# octanis_eps_compact_no_OPA2333.net
KiCad netlist of a schematic drawn in EAGLE
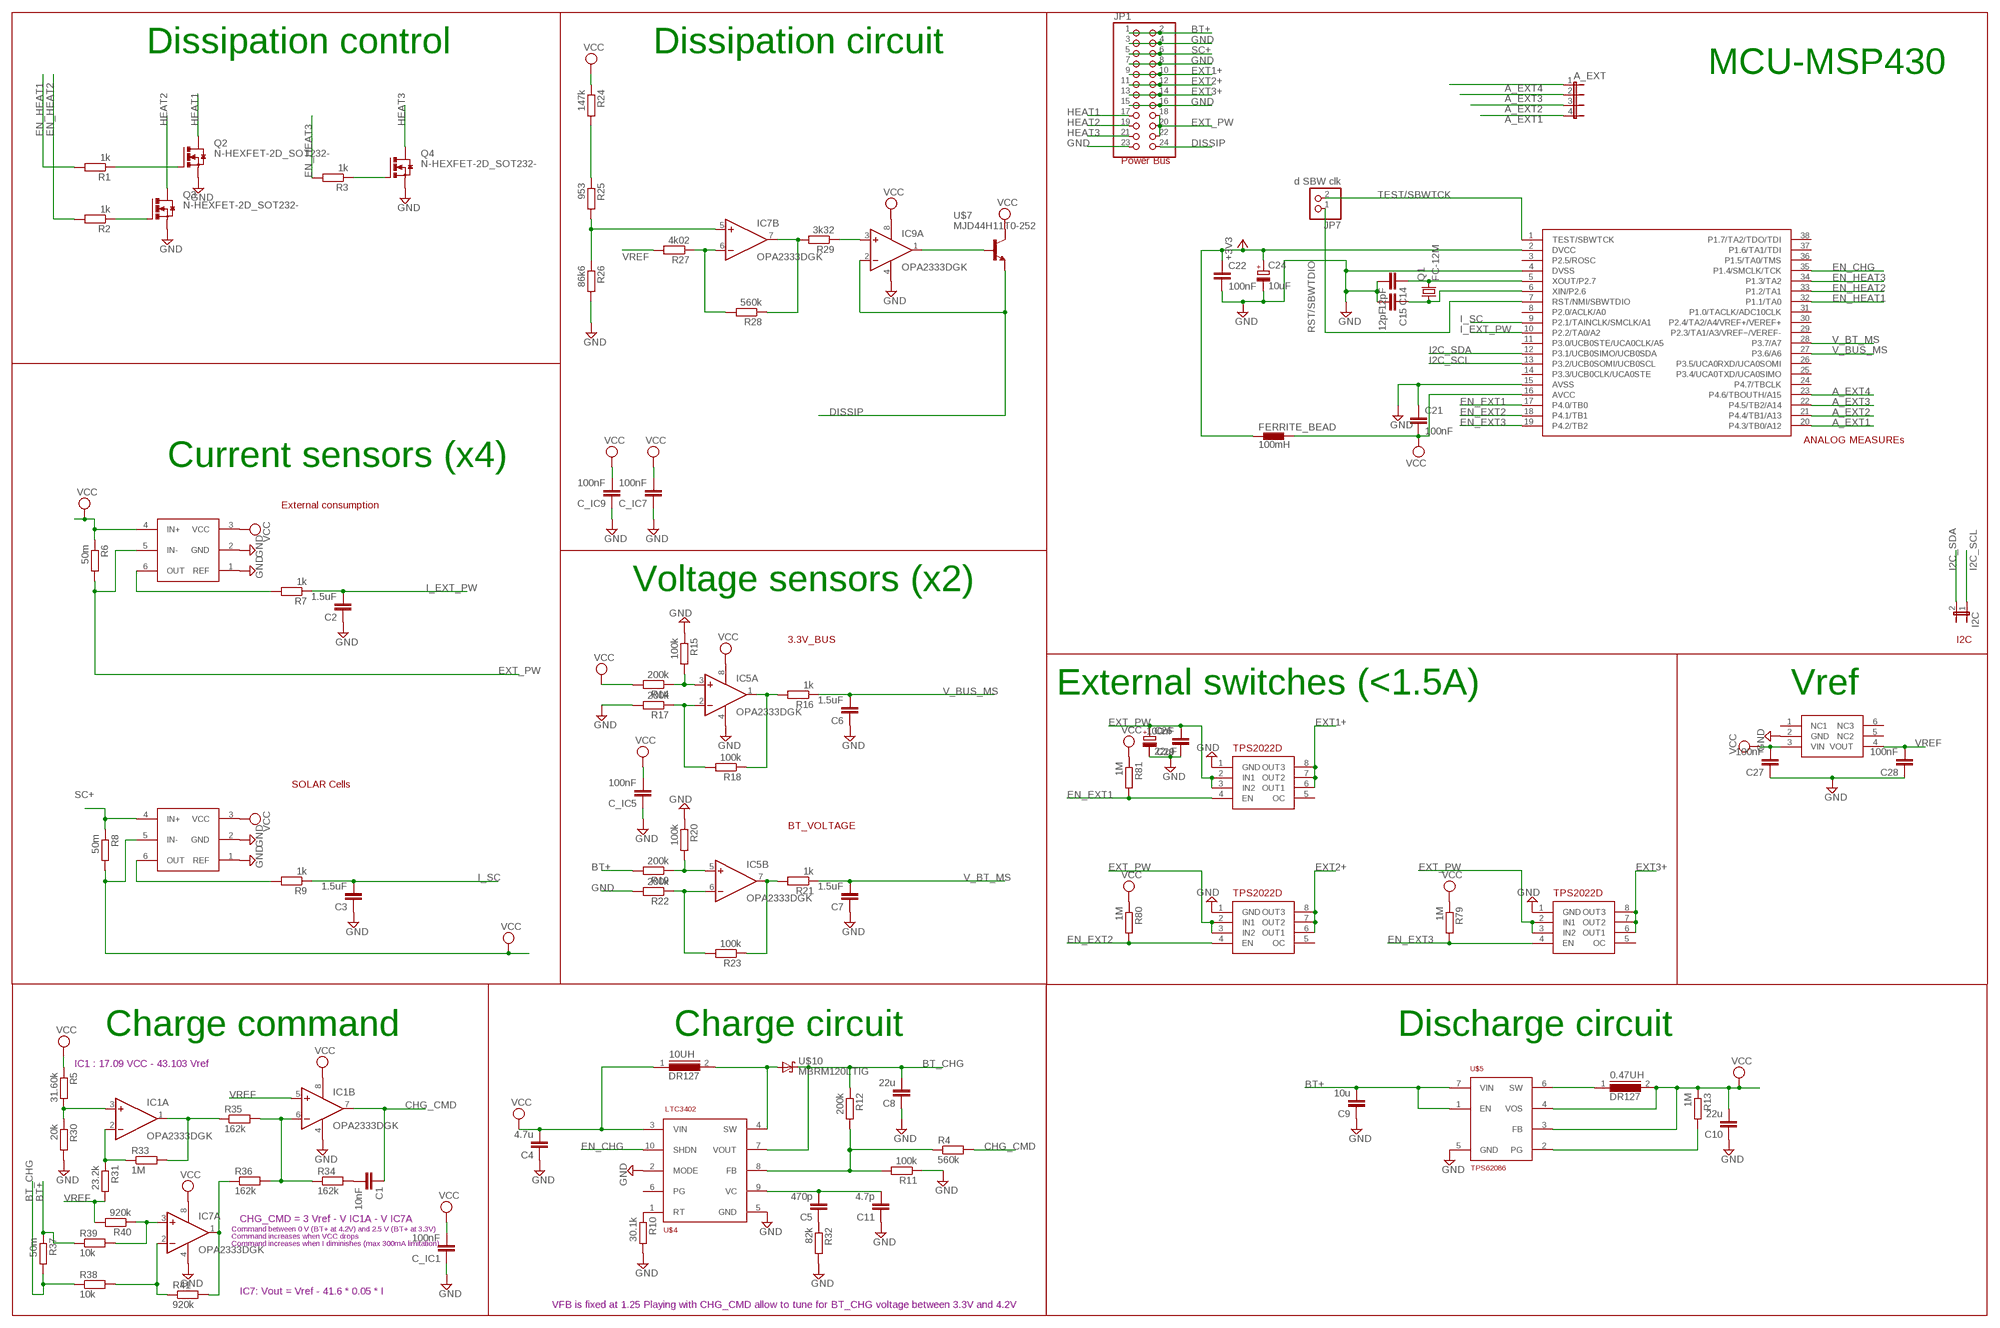
[diagram p0: schematic, sheet 1]

(export (version "E")
  (design (tool "Eeschema 10.0.6"))
  (components
    (comp (ref "0.47UH")
      (value "DR127")
      (footprint "eagle-import:DR127")
      (libsource (lib "eagle-import") (part "DR127"))
    )
    (comp (ref "10UH")
      (value "DR127")
      (footprint "eagle-import:DR127")
      (libsource (lib "eagle-import") (part "DR127"))
    )
    (comp (ref "A_EXT")
      (value "JP4E")
      (footprint "eagle-import:JP4")
      (libsource (lib "eagle-import") (part "JP4E"))
    )
    (comp (ref "C1")
      (value "10nF")
      (footprint "eagle-import:C0603")
      (libsource (lib "eagle-import") (part "C-EUC0603"))
    )
    (comp (ref "C2")
      (value "1.5uF")
      (footprint "eagle-import:C0603")
      (libsource (lib "eagle-import") (part "C-EUC0603"))
    )
    (comp (ref "C3")
      (value "1.5uF")
      (footprint "eagle-import:C0603")
      (libsource (lib "eagle-import") (part "C-EUC0603"))
    )
    (comp (ref "C4")
      (value "4.7u")
      (footprint "eagle-import:C1206")
      (libsource (lib "eagle-import") (part "C-EUC1206"))
    )
    (comp (ref "C5")
      (value "470p")
      (footprint "eagle-import:C0603")
      (libsource (lib "eagle-import") (part "C-EUC0603"))
    )
    (comp (ref "C6")
      (value "1.5uF")
      (footprint "eagle-import:C0603")
      (libsource (lib "eagle-import") (part "C-EUC0603"))
    )
    (comp (ref "C7")
      (value "1.5uF")
      (footprint "eagle-import:C0603")
      (libsource (lib "eagle-import") (part "C-EUC0603"))
    )
    (comp (ref "C8")
      (value "22u")
      (footprint "eagle-import:C0603")
      (libsource (lib "eagle-import") (part "C-EUC0603"))
    )
    (comp (ref "C9")
      (value "10u")
      (footprint "eagle-import:C1206")
      (libsource (lib "eagle-import") (part "C-EUC1206"))
    )
    (comp (ref "C10")
      (value "22u")
      (footprint "eagle-import:C1206")
      (libsource (lib "eagle-import") (part "C-EUC1206"))
    )
    (comp (ref "C11")
      (value "4.7p")
      (footprint "eagle-import:C0603")
      (libsource (lib "eagle-import") (part "C-EUC0603"))
    )
    (comp (ref "C14")
      (value "12pF")
      (footprint "eagle-import:C0603")
      (libsource (lib "eagle-import") (part "C-EUC0603"))
    )
    (comp (ref "C15")
      (value "12pF")
      (footprint "eagle-import:C0603")
      (libsource (lib "eagle-import") (part "C-EUC0603"))
    )
    (comp (ref "C21")
      (value "100nF")
      (footprint "eagle-import:C0603")
      (libsource (lib "eagle-import") (part "C-EUC0603"))
    )
    (comp (ref "C22")
      (value "100nF")
      (footprint "eagle-import:C0603")
      (libsource (lib "eagle-import") (part "C-EUC0603"))
    )
    (comp (ref "C24")
      (value "10uF")
      (footprint "eagle-import:A_3216-18R")
      (libsource (lib "eagle-import") (part "CPOL-EUA/3216-18R"))
    )
    (comp (ref "C26")
      (value "22uF")
      (footprint "eagle-import:A_3216-18R")
      (libsource (lib "eagle-import") (part "CPOL-EUA/3216-18R"))
    )
    (comp (ref "C27")
      (value "100nF")
      (footprint "eagle-import:C0603")
      (libsource (lib "eagle-import") (part "C-EUC0603"))
    )
    (comp (ref "C28")
      (value "100nF")
      (footprint "eagle-import:C0603")
      (libsource (lib "eagle-import") (part "C-EUC0603"))
    )
    (comp (ref "C29")
      (value "100nF")
      (footprint "eagle-import:C0603")
      (libsource (lib "eagle-import") (part "C-EUC0603"))
    )
    (comp (ref "C_IC1")
      (value "100nF")
      (footprint "eagle-import:C0603")
      (libsource (lib "eagle-import") (part "C-EUC0603"))
    )
    (comp (ref "C_IC5")
      (value "100nF")
      (footprint "eagle-import:C0603")
      (libsource (lib "eagle-import") (part "C-EUC0603"))
    )
    (comp (ref "C_IC7")
      (value "100nF")
      (footprint "eagle-import:C0603")
      (libsource (lib "eagle-import") (part "C-EUC0603"))
    )
    (comp (ref "C_IC9")
      (value "100nF")
      (footprint "eagle-import:C0603")
      (libsource (lib "eagle-import") (part "C-EUC0603"))
    )
    (comp (ref "FERRITE_BEAD")
      (value "100mH")
      (footprint "eagle-import:0402")
      (libsource (lib "eagle-import") (part "BLM15HD601SN1"))
    )
    (comp (ref "I2C")
      (value "JP1E")
      (footprint "eagle-import:JP1")
      (libsource (lib "eagle-import") (part "JP1E"))
    )
    (comp (ref "IC1")
      (value "OPA2333DGK")
      (footprint "eagle-import:MSOP08")
      (libsource (lib "eagle-import") (part "OPA2333DGK"))
    )
    (comp (ref "IC5")
      (value "OPA2333DGK")
      (footprint "eagle-import:MSOP08")
      (libsource (lib "eagle-import") (part "OPA2333DGK"))
    )
    (comp (ref "IC7")
      (value "OPA2333DGK")
      (footprint "eagle-import:MSOP08")
      (libsource (lib "eagle-import") (part "OPA2333DGK"))
    )
    (comp (ref "IC9")
      (value "OPA2333DGK")
      (footprint "eagle-import:MSOP08")
      (libsource (lib "eagle-import") (part "OPA2333DGK"))
    )
    (comp (ref "JP1")
      (value "PINHD-2X12")
      (footprint "eagle-import:2X12")
      (libsource (lib "eagle-import") (part "PINHD-2X12"))
    )
    (comp (ref "JP7")
      (value "d SBW clk")
      (footprint "eagle-import:1X02")
      (libsource (lib "eagle-import") (part "PINHD-1X2"))
    )
    (comp (ref "Q1")
      (value "FC-12M")
      (footprint "eagle-import:FC-12M")
      (libsource (lib "eagle-import") (part "FC-12M"))
    )
    (comp (ref "Q2")
      (value "N-HEXFET-2D_SOT232-")
      (footprint "eagle-import:SOT223")
      (libsource (lib "eagle-import") (part "N-HEXFET-2D_?-SOT232"))
    )
    (comp (ref "Q3")
      (value "N-HEXFET-2D_SOT232-")
      (footprint "eagle-import:SOT223")
      (libsource (lib "eagle-import") (part "N-HEXFET-2D_?-SOT232"))
    )
    (comp (ref "Q4")
      (value "N-HEXFET-2D_SOT232-")
      (footprint "eagle-import:SOT223")
      (libsource (lib "eagle-import") (part "N-HEXFET-2D_?-SOT232"))
    )
    (comp (ref "R1")
      (value "1k")
      (footprint "eagle-import:R0603")
      (libsource (lib "eagle-import") (part "R-EU_R0603"))
    )
    (comp (ref "R2")
      (value "1k")
      (footprint "eagle-import:R0603")
      (libsource (lib "eagle-import") (part "R-EU_R0603"))
    )
    (comp (ref "R3")
      (value "1k")
      (footprint "eagle-import:R0603")
      (libsource (lib "eagle-import") (part "R-EU_R0603"))
    )
    (comp (ref "R4")
      (value "560k")
      (footprint "eagle-import:R0603")
      (libsource (lib "eagle-import") (part "R-EU_R0603"))
    )
    (comp (ref "R5")
      (value "31.60k")
      (footprint "eagle-import:R0603")
      (libsource (lib "eagle-import") (part "R-EU_R0603"))
    )
    (comp (ref "R6")
      (value "50m")
      (footprint "eagle-import:R1206")
      (libsource (lib "eagle-import") (part "R-EU_R1206"))
    )
    (comp (ref "R7")
      (value "1k")
      (footprint "eagle-import:R0603")
      (libsource (lib "eagle-import") (part "R-EU_R0603"))
    )
    (comp (ref "R8")
      (value "50m")
      (footprint "eagle-import:R1206")
      (libsource (lib "eagle-import") (part "R-EU_R1206"))
    )
    (comp (ref "R9")
      (value "1k")
      (footprint "eagle-import:R0603")
      (libsource (lib "eagle-import") (part "R-EU_R0603"))
    )
    (comp (ref "R10")
      (value "30.1k")
      (footprint "eagle-import:R0603")
      (libsource (lib "eagle-import") (part "R-EU_R0603"))
    )
    (comp (ref "R11")
      (value "100k")
      (footprint "eagle-import:R0603")
      (libsource (lib "eagle-import") (part "R-EU_R0603"))
    )
    (comp (ref "R12")
      (value "200k")
      (footprint "eagle-import:R0603")
      (libsource (lib "eagle-import") (part "R-EU_R0603"))
    )
    (comp (ref "R13")
      (value "1M")
      (footprint "eagle-import:R0603")
      (libsource (lib "eagle-import") (part "R-EU_R0603"))
    )
    (comp (ref "R14")
      (value "200k")
      (footprint "eagle-import:R0603")
      (libsource (lib "eagle-import") (part "R-EU_R0603"))
    )
    (comp (ref "R15")
      (value "100k")
      (footprint "eagle-import:R0603")
      (libsource (lib "eagle-import") (part "R-EU_R0603"))
    )
    (comp (ref "R16")
      (value "1k")
      (footprint "eagle-import:R0603")
      (libsource (lib "eagle-import") (part "R-EU_R0603"))
    )
    (comp (ref "R17")
      (value "200k")
      (footprint "eagle-import:R0603")
      (libsource (lib "eagle-import") (part "R-EU_R0603"))
    )
    (comp (ref "R18")
      (value "100k")
      (footprint "eagle-import:R0603")
      (libsource (lib "eagle-import") (part "R-EU_R0603"))
    )
    (comp (ref "R19")
      (value "200k")
      (footprint "eagle-import:R0603")
      (libsource (lib "eagle-import") (part "R-EU_R0603"))
    )
    (comp (ref "R20")
      (value "100k")
      (footprint "eagle-import:R0603")
      (libsource (lib "eagle-import") (part "R-EU_R0603"))
    )
    (comp (ref "R21")
      (value "1k")
      (footprint "eagle-import:R0603")
      (libsource (lib "eagle-import") (part "R-EU_R0603"))
    )
    (comp (ref "R22")
      (value "200k")
      (footprint "eagle-import:R0603")
      (libsource (lib "eagle-import") (part "R-EU_R0603"))
    )
    (comp (ref "R23")
      (value "100k")
      (footprint "eagle-import:R0603")
      (libsource (lib "eagle-import") (part "R-EU_R0603"))
    )
    (comp (ref "R24")
      (value "147k")
      (footprint "eagle-import:R0603")
      (libsource (lib "eagle-import") (part "R-EU_R0603"))
    )
    (comp (ref "R25")
      (value "953")
      (footprint "eagle-import:R0603")
      (libsource (lib "eagle-import") (part "R-EU_R0603"))
    )
    (comp (ref "R26")
      (value "86k6")
      (footprint "eagle-import:R0603")
      (libsource (lib "eagle-import") (part "R-EU_R0603"))
    )
    (comp (ref "R27")
      (value "4k02")
      (footprint "eagle-import:R0603")
      (libsource (lib "eagle-import") (part "R-EU_R0603"))
    )
    (comp (ref "R28")
      (value "560k")
      (footprint "eagle-import:R0603")
      (libsource (lib "eagle-import") (part "R-EU_R0603"))
    )
    (comp (ref "R29")
      (value "3k32")
      (footprint "eagle-import:R0603")
      (libsource (lib "eagle-import") (part "R-EU_R0603"))
    )
    (comp (ref "R30")
      (value "20k")
      (footprint "eagle-import:R0603")
      (libsource (lib "eagle-import") (part "R-EU_R0603"))
    )
    (comp (ref "R31")
      (value "23.2k")
      (footprint "eagle-import:R0603")
      (libsource (lib "eagle-import") (part "R-EU_R0603"))
    )
    (comp (ref "R32")
      (value "82k")
      (footprint "eagle-import:R0603")
      (libsource (lib "eagle-import") (part "R-EU_R0603"))
    )
    (comp (ref "R33")
      (value "1M")
      (footprint "eagle-import:R0603")
      (libsource (lib "eagle-import") (part "R-EU_R0603"))
    )
    (comp (ref "R34")
      (value "162k")
      (footprint "eagle-import:R0603")
      (libsource (lib "eagle-import") (part "R-EU_R0603"))
    )
    (comp (ref "R35")
      (value "162k")
      (footprint "eagle-import:R0603")
      (libsource (lib "eagle-import") (part "R-EU_R0603"))
    )
    (comp (ref "R36")
      (value "162k")
      (footprint "eagle-import:R0603")
      (libsource (lib "eagle-import") (part "R-EU_R0603"))
    )
    (comp (ref "R37")
      (value "50m")
      (footprint "eagle-import:R1206")
      (libsource (lib "eagle-import") (part "R-EU_R1206"))
    )
    (comp (ref "R38")
      (value "10k")
      (footprint "eagle-import:R0603")
      (libsource (lib "eagle-import") (part "R-EU_R0603"))
    )
    (comp (ref "R39")
      (value "10k")
      (footprint "eagle-import:R0603")
      (libsource (lib "eagle-import") (part "R-EU_R0603"))
    )
    (comp (ref "R40")
      (value "920k")
      (footprint "eagle-import:R0603")
      (libsource (lib "eagle-import") (part "R-EU_R0603"))
    )
    (comp (ref "R41")
      (value "920k")
      (footprint "eagle-import:R0603")
      (libsource (lib "eagle-import") (part "R-EU_R0603"))
    )
    (comp (ref "R79")
      (value "1M")
      (footprint "eagle-import:R0603")
      (libsource (lib "eagle-import") (part "R-EU_R0603"))
    )
    (comp (ref "R80")
      (value "1M")
      (footprint "eagle-import:R0603")
      (libsource (lib "eagle-import") (part "R-EU_R0603"))
    )
    (comp (ref "R81")
      (value "1M")
      (footprint "eagle-import:R0603")
      (libsource (lib "eagle-import") (part "R-EU_R0603"))
    )
    (comp (ref "U$2")
      (value "INA213")
      (footprint "eagle-import:SC70-6")
      (libsource (lib "eagle-import") (part "INA213"))
    )
    (comp (ref "U$3")
      (value "INA213")
      (footprint "eagle-import:SC70-6")
      (libsource (lib "eagle-import") (part "INA213"))
    )
    (comp (ref "U$4")
      (value "LTC3402")
      (footprint "eagle-import:MSOP10")
      (libsource (lib "eagle-import") (part "LTC3402"))
    )
    (comp (ref "U$5")
      (value "TPS62086")
      (footprint "eagle-import:QFN-7")
      (libsource (lib "eagle-import") (part "TPS62086"))
    )
    (comp (ref "U$6")
      (value "MSP430G2544")
      (footprint "eagle-import:TSSOP38")
      (libsource (lib "eagle-import") (part "MSP430G2544"))
    )
    (comp (ref "U$7")
      (value "MJD44H11T0-252")
      (footprint "eagle-import:TO252")
      (libsource (lib "eagle-import") (part "MJD44H11T0-252"))
    )
    (comp (ref "U$10")
      (value "MBRM120LTIG")
      (footprint "eagle-import:DO216AA")
      (libsource (lib "eagle-import") (part "MBRM120LTIG"))
    )
    (comp (ref "U$16")
      (value "TPS2022D")
      (footprint "eagle-import:SO8")
      (libsource (lib "eagle-import") (part "TPS2022D"))
    )
    (comp (ref "U$17")
      (value "TPS2022D")
      (footprint "eagle-import:SO8")
      (libsource (lib "eagle-import") (part "TPS2022D"))
    )
    (comp (ref "U$18")
      (value "TPS2022D")
      (footprint "eagle-import:SO8")
      (libsource (lib "eagle-import") (part "TPS2022D"))
    )
    (comp (ref "U$19")
      (value "ADR127B")
      (footprint "eagle-import:TSOT23-6")
      (libsource (lib "eagle-import") (part "ADR127B"))
    )
  )
  (nets
    (net (code "1") (name "+3V3") (class "Default")
      (node (ref "C22") (pin "1") (pinfunction "1_1") (pintype "passive"))
      (node (ref "C24") (pin "+") (pinfunction "+_+") (pintype "passive"))
      (node (ref "FERRITE_BEAD") (pin "1") (pinfunction "1_1") (pintype "passive"))
      (node (ref "U$6") (pin "2") (pinfunction "DVCC_2") (pintype "bidirectional"))
    )
    (net (code "2") (name "/A_EXT1") (class "Default")
      (node (ref "A_EXT") (pin "4") (pinfunction "4_4") (pintype "passive"))
      (node (ref "U$6") (pin "20") (pinfunction "P4.3/TB0/A12_20") (pintype "bidirectional"))
    )
    (net (code "3") (name "/A_EXT2") (class "Default")
      (node (ref "A_EXT") (pin "3") (pinfunction "3_3") (pintype "passive"))
      (node (ref "U$6") (pin "21") (pinfunction "P4.4/TB1/A13_21") (pintype "bidirectional"))
    )
    (net (code "4") (name "/A_EXT3") (class "Default")
      (node (ref "A_EXT") (pin "2") (pinfunction "2_2") (pintype "passive"))
      (node (ref "U$6") (pin "22") (pinfunction "P4.5/TB2/A14_22") (pintype "bidirectional"))
    )
    (net (code "5") (name "/A_EXT4") (class "Default")
      (node (ref "A_EXT") (pin "1") (pinfunction "1_1") (pintype "passive"))
      (node (ref "U$6") (pin "23") (pinfunction "P4.6/TBOUTH/A15_23") (pintype "bidirectional"))
    )
    (net (code "6") (name "/BT+") (class "Default")
      (node (ref "C9") (pin "2") (pinfunction "2_2") (pintype "passive"))
      (node (ref "JP1") (pin "1") (pinfunction "1_1") (pintype "passive"))
      (node (ref "JP1") (pin "2") (pinfunction "2_2") (pintype "passive"))
      (node (ref "R19") (pin "2") (pinfunction "2_2") (pintype "passive"))
      (node (ref "R37") (pin "1") (pinfunction "1_1") (pintype "passive"))
      (node (ref "R39") (pin "1") (pinfunction "1_1") (pintype "passive"))
      (node (ref "U$5") (pin "1") (pinfunction "EN_1") (pintype "bidirectional"))
      (node (ref "U$5") (pin "7") (pinfunction "VIN_7") (pintype "bidirectional"))
    )
    (net (code "7") (name "/BT_CHG") (class "Default")
      (node (ref "C8") (pin "2") (pinfunction "2_2") (pintype "passive"))
      (node (ref "R12") (pin "1") (pinfunction "1_1") (pintype "passive"))
      (node (ref "R37") (pin "2") (pinfunction "2_2") (pintype "passive"))
      (node (ref "R38") (pin "1") (pinfunction "1_1") (pintype "passive"))
      (node (ref "U$10") (pin "C") (pinfunction "K_C") (pintype "passive"))
      (node (ref "U$4") (pin "7") (pinfunction "VOUT_7") (pintype "bidirectional"))
    )
    (net (code "8") (name "/CHG_CMD") (class "Default")
      (node (ref "C1") (pin "1") (pinfunction "1_1") (pintype "passive"))
      (node (ref "IC1") (pin "7") (pinfunction "OUT_7") (pintype "output"))
      (node (ref "R4") (pin "2") (pinfunction "2_2") (pintype "passive"))
    )
    (net (code "9") (name "/DISSIP") (class "Default")
      (node (ref "IC9") (pin "2") (pinfunction "-IN_2") (pintype "input"))
      (node (ref "JP1") (pin "24") (pinfunction "24_24") (pintype "passive"))
      (node (ref "U$7") (pin "3") (pinfunction "E_3") (pintype "passive"))
    )
    (net (code "10") (name "/EN_CHG") (class "Default")
      (node (ref "U$4") (pin "10") (pinfunction "SHDN_10") (pintype "bidirectional"))
      (node (ref "U$6") (pin "35") (pinfunction "P1.4/SMCLK/TCK_35") (pintype "bidirectional"))
    )
    (net (code "11") (name "/EN_EXT1") (class "Default")
      (node (ref "R81") (pin "2") (pinfunction "2_2") (pintype "passive"))
      (node (ref "U$16") (pin "4") (pinfunction "EN_4") (pintype "bidirectional"))
      (node (ref "U$6") (pin "17") (pinfunction "P4.0/TB0_17") (pintype "bidirectional"))
    )
    (net (code "12") (name "/EN_EXT2") (class "Default")
      (node (ref "R80") (pin "2") (pinfunction "2_2") (pintype "passive"))
      (node (ref "U$17") (pin "4") (pinfunction "EN_4") (pintype "bidirectional"))
      (node (ref "U$6") (pin "18") (pinfunction "P4.1/TB1_18") (pintype "bidirectional"))
    )
    (net (code "13") (name "/EN_EXT3") (class "Default")
      (node (ref "R79") (pin "2") (pinfunction "2_2") (pintype "passive"))
      (node (ref "U$18") (pin "4") (pinfunction "EN_4") (pintype "bidirectional"))
      (node (ref "U$6") (pin "19") (pinfunction "P4.2/TB2_19") (pintype "bidirectional"))
    )
    (net (code "14") (name "/EN_HEAT1") (class "Default")
      (node (ref "R1") (pin "2") (pinfunction "2_2") (pintype "passive"))
      (node (ref "U$6") (pin "32") (pinfunction "P1.1/TA0_32") (pintype "bidirectional"))
    )
    (net (code "15") (name "/EN_HEAT2") (class "Default")
      (node (ref "R2") (pin "2") (pinfunction "2_2") (pintype "passive"))
      (node (ref "U$6") (pin "33") (pinfunction "P1.2/TA1_33") (pintype "bidirectional"))
    )
    (net (code "16") (name "/EN_HEAT3") (class "Default")
      (node (ref "R3") (pin "2") (pinfunction "2_2") (pintype "passive"))
      (node (ref "U$6") (pin "34") (pinfunction "P1.3/TA2_34") (pintype "bidirectional"))
    )
    (net (code "17") (name "/EXT1+") (class "Default")
      (node (ref "JP1") (pin "10") (pinfunction "10_10") (pintype "passive"))
      (node (ref "JP1") (pin "9") (pinfunction "9_9") (pintype "passive"))
      (node (ref "U$16") (pin "6") (pinfunction "OUT1_6") (pintype "bidirectional"))
      (node (ref "U$16") (pin "7") (pinfunction "OUT2_7") (pintype "bidirectional"))
      (node (ref "U$16") (pin "8") (pinfunction "OUT3_8") (pintype "bidirectional"))
    )
    (net (code "18") (name "/EXT2+") (class "Default")
      (node (ref "JP1") (pin "11") (pinfunction "11_11") (pintype "passive"))
      (node (ref "JP1") (pin "12") (pinfunction "12_12") (pintype "passive"))
      (node (ref "U$17") (pin "6") (pinfunction "OUT1_6") (pintype "bidirectional"))
      (node (ref "U$17") (pin "7") (pinfunction "OUT2_7") (pintype "bidirectional"))
      (node (ref "U$17") (pin "8") (pinfunction "OUT3_8") (pintype "bidirectional"))
    )
    (net (code "19") (name "/EXT3+") (class "Default")
      (node (ref "JP1") (pin "13") (pinfunction "13_13") (pintype "passive"))
      (node (ref "JP1") (pin "14") (pinfunction "14_14") (pintype "passive"))
      (node (ref "U$18") (pin "6") (pinfunction "OUT1_6") (pintype "bidirectional"))
      (node (ref "U$18") (pin "7") (pinfunction "OUT2_7") (pintype "bidirectional"))
      (node (ref "U$18") (pin "8") (pinfunction "OUT3_8") (pintype "bidirectional"))
    )
    (net (code "20") (name "/EXT_PW") (class "Default")
      (node (ref "C26") (pin "+") (pinfunction "+_+") (pintype "passive"))
      (node (ref "C29") (pin "2") (pinfunction "2_2") (pintype "passive"))
      (node (ref "JP1") (pin "18") (pinfunction "18_18") (pintype "passive"))
      (node (ref "JP1") (pin "20") (pinfunction "20_20") (pintype "passive"))
      (node (ref "JP1") (pin "22") (pinfunction "22_22") (pintype "passive"))
      (node (ref "R6") (pin "2") (pinfunction "2_2") (pintype "passive"))
      (node (ref "U$16") (pin "2") (pinfunction "IN1_2") (pintype "bidirectional"))
      (node (ref "U$16") (pin "3") (pinfunction "IN2_3") (pintype "bidirectional"))
      (node (ref "U$17") (pin "2") (pinfunction "IN1_2") (pintype "bidirectional"))
      (node (ref "U$17") (pin "3") (pinfunction "IN2_3") (pintype "bidirectional"))
      (node (ref "U$18") (pin "2") (pinfunction "IN1_2") (pintype "bidirectional"))
      (node (ref "U$18") (pin "3") (pinfunction "IN2_3") (pintype "bidirectional"))
      (node (ref "U$2") (pin "5") (pinfunction "IN-_5") (pintype "bidirectional"))
    )
    (net (code "21") (name "/HEAT1") (class "Default")
      (node (ref "JP1") (pin "17") (pinfunction "17_17") (pintype "passive"))
      (node (ref "Q2") (pin "2") (pinfunction "D_2") (pintype "passive"))
      (node (ref "Q2") (pin "4") (pinfunction "D_4") (pintype "passive"))
    )
    (net (code "22") (name "/HEAT2") (class "Default")
      (node (ref "JP1") (pin "19") (pinfunction "19_19") (pintype "passive"))
      (node (ref "Q3") (pin "2") (pinfunction "D_2") (pintype "passive"))
      (node (ref "Q3") (pin "4") (pinfunction "D_4") (pintype "passive"))
    )
    (net (code "23") (name "/HEAT3") (class "Default")
      (node (ref "JP1") (pin "21") (pinfunction "21_21") (pintype "passive"))
      (node (ref "Q4") (pin "2") (pinfunction "D_2") (pintype "passive"))
      (node (ref "Q4") (pin "4") (pinfunction "D_4") (pintype "passive"))
    )
    (net (code "24") (name "/I2C_SCL") (class "Default")
      (node (ref "I2C") (pin "1") (pinfunction "1_1") (pintype "passive"))
      (node (ref "U$6") (pin "13") (pinfunction "P3.2/UCB0SOMI/UCB0SCL_13") (pintype "bidirectional"))
    )
    (net (code "25") (name "/I2C_SDA") (class "Default")
      (node (ref "I2C") (pin "2") (pinfunction "2_2") (pintype "passive"))
      (node (ref "U$6") (pin "12") (pinfunction "P3.1/UCB0SIMO/UCB0SDA_12") (pintype "bidirectional"))
    )
    (net (code "26") (name "/I_EXT_PW") (class "Default")
      (node (ref "C2") (pin "2") (pinfunction "2_2") (pintype "passive"))
      (node (ref "R7") (pin "1") (pinfunction "1_1") (pintype "passive"))
      (node (ref "U$6") (pin "10") (pinfunction "P2.2/TA0/A2_10") (pintype "bidirectional"))
    )
    (net (code "27") (name "/I_SC") (class "Default")
      (node (ref "C3") (pin "2") (pinfunction "2_2") (pintype "passive"))
      (node (ref "R9") (pin "1") (pinfunction "1_1") (pintype "passive"))
      (node (ref "U$6") (pin "9") (pinfunction "P2.1/TAINCLK/SMCLK/A1_9") (pintype "bidirectional"))
    )
    (net (code "28") (name "/RST{slash}SBWTDIO") (class "Default")
      (node (ref "JP7") (pin "1") (pinfunction "1_1") (pintype "passive"))
      (node (ref "U$6") (pin "7") (pinfunction "RST/NMI/SBWTDIO_7") (pintype "bidirectional"))
    )
    (net (code "29") (name "/SC+") (class "Default")
      (node (ref "JP1") (pin "5") (pinfunction "5_5") (pintype "passive"))
      (node (ref "JP1") (pin "6") (pinfunction "6_6") (pintype "passive"))
      (node (ref "R8") (pin "1") (pinfunction "1_1") (pintype "passive"))
      (node (ref "U$3") (pin "4") (pinfunction "IN+_4") (pintype "bidirectional"))
    )
    (net (code "30") (name "/TEST{slash}SBWTCK") (class "Default")
      (node (ref "JP7") (pin "2") (pinfunction "2_2") (pintype "passive"))
      (node (ref "U$6") (pin "1") (pinfunction "TEST/SBWTCK_1") (pintype "bidirectional"))
    )
    (net (code "31") (name "/VREF") (class "Default")
      (node (ref "C28") (pin "2") (pinfunction "2_2") (pintype "passive"))
      (node (ref "IC1") (pin "5") (pinfunction "+IN_5") (pintype "input"))
      (node (ref "R27") (pin "2") (pinfunction "2_2") (pintype "passive"))
      (node (ref "R31") (pin "2") (pinfunction "2_2") (pintype "passive"))
      (node (ref "R40") (pin "2") (pinfunction "2_2") (pintype "passive"))
      (node (ref "U$19") (pin "4") (pinfunction "VOUT_4") (pintype "bidirectional"))
    )
    (net (code "32") (name "/V_BT_MS") (class "Default")
      (node (ref "C7") (pin "2") (pinfunction "2_2") (pintype "passive"))
      (node (ref "R21") (pin "1") (pinfunction "1_1") (pintype "passive"))
      (node (ref "U$6") (pin "28") (pinfunction "P3.7/A7_28") (pintype "bidirectional"))
    )
    (net (code "33") (name "/V_BUS_MS") (class "Default")
      (node (ref "C6") (pin "2") (pinfunction "2_2") (pintype "passive"))
      (node (ref "R16") (pin "1") (pinfunction "1_1") (pintype "passive"))
      (node (ref "U$6") (pin "27") (pinfunction "P3.6/A6_27") (pintype "bidirectional"))
    )
    (net (code "34") (name "GND") (class "Default")
      (node (ref "C10") (pin "1") (pinfunction "1_1") (pintype "passive"))
      (node (ref "C11") (pin "1") (pinfunction "1_1") (pintype "passive"))
      (node (ref "C14") (pin "2") (pinfunction "2_2") (pintype "passive"))
      (node (ref "C15") (pin "2") (pinfunction "2_2") (pintype "passive"))
      (node (ref "C2") (pin "1") (pinfunction "1_1") (pintype "passive"))
      (node (ref "C21") (pin "1") (pinfunction "1_1") (pintype "passive"))
      (node (ref "C22") (pin "2") (pinfunction "2_2") (pintype "passive"))
      (node (ref "C24") (pin "-") (pinfunction "-_-") (pintype "passive"))
      (node (ref "C26") (pin "-") (pinfunction "-_-") (pintype "passive"))
      (node (ref "C27") (pin "1") (pinfunction "1_1") (pintype "passive"))
      (node (ref "C28") (pin "1") (pinfunction "1_1") (pintype "passive"))
      (node (ref "C29") (pin "1") (pinfunction "1_1") (pintype "passive"))
      (node (ref "C3") (pin "1") (pinfunction "1_1") (pintype "passive"))
      (node (ref "C4") (pin "1") (pinfunction "1_1") (pintype "passive"))
      (node (ref "C6") (pin "1") (pinfunction "1_1") (pintype "passive"))
      (node (ref "C7") (pin "1") (pinfunction "1_1") (pintype "passive"))
      (node (ref "C8") (pin "1") (pinfunction "1_1") (pintype "passive"))
      (node (ref "C9") (pin "1") (pinfunction "1_1") (pintype "passive"))
      (node (ref "C_IC1") (pin "1") (pinfunction "1_1") (pintype "passive"))
      (node (ref "C_IC5") (pin "1") (pinfunction "1_1") (pintype "passive"))
      (node (ref "C_IC7") (pin "1") (pinfunction "1_1") (pintype "passive"))
      (node (ref "C_IC9") (pin "1") (pinfunction "1_1") (pintype "passive"))
      (node (ref "IC1") (pin "4") (pinfunction "V-_4") (pintype "power_in"))
      (node (ref "IC5") (pin "4") (pinfunction "V-_4") (pintype "power_in"))
      (node (ref "IC7") (pin "4") (pinfunction "V-_4") (pintype "power_in"))
      (node (ref "IC9") (pin "4") (pinfunction "V-_4") (pintype "power_in"))
      (node (ref "JP1") (pin "15") (pinfunction "15_15") (pintype "passive"))
      (node (ref "JP1") (pin "16") (pinfunction "16_16") (pintype "passive"))
      (node (ref "JP1") (pin "23") (pinfunction "23_23") (pintype "passive"))
      (node (ref "JP1") (pin "3") (pinfunction "3_3") (pintype "passive"))
      (node (ref "JP1") (pin "4") (pinfunction "4_4") (pintype "passive"))
      (node (ref "JP1") (pin "7") (pinfunction "7_7") (pintype "passive"))
      (node (ref "JP1") (pin "8") (pinfunction "8_8") (pintype "passive"))
      (node (ref "Q2") (pin "3") (pinfunction "S_3") (pintype "passive"))
      (node (ref "Q3") (pin "3") (pinfunction "S_3") (pintype "passive"))
      (node (ref "Q4") (pin "3") (pinfunction "S_3") (pintype "passive"))
      (node (ref "R10") (pin "2") (pinfunction "2_2") (pintype "passive"))
      (node (ref "R11") (pin "1") (pinfunction "1_1") (pintype "passive"))
      (node (ref "R15") (pin "1") (pinfunction "1_1") (pintype "passive"))
      (node (ref "R17") (pin "2") (pinfunction "2_2") (pintype "passive"))
      (node (ref "R20") (pin "1") (pinfunction "1_1") (pintype "passive"))
      (node (ref "R22") (pin "2") (pinfunction "2_2") (pintype "passive"))
      (node (ref "R26") (pin "2") (pinfunction "2_2") (pintype "passive"))
      (node (ref "R30") (pin "2") (pinfunction "2_2") (pintype "passive"))
      (node (ref "R32") (pin "2") (pinfunction "2_2") (pintype "passive"))
      (node (ref "U$16") (pin "1") (pinfunction "GND_1") (pintype "bidirectional"))
      (node (ref "U$17") (pin "1") (pinfunction "GND_1") (pintype "bidirectional"))
      (node (ref "U$18") (pin "1") (pinfunction "GND_1") (pintype "bidirectional"))
      (node (ref "U$19") (pin "2") (pinfunction "GND_2") (pintype "bidirectional"))
      (node (ref "U$2") (pin "1") (pinfunction "REF_1") (pintype "bidirectional"))
      (node (ref "U$2") (pin "2") (pinfunction "GND_2") (pintype "bidirectional"))
      (node (ref "U$3") (pin "1") (pinfunction "REF_1") (pintype "bidirectional"))
      (node (ref "U$3") (pin "2") (pinfunction "GND_2") (pintype "bidirectional"))
      (node (ref "U$4") (pin "2") (pinfunction "MODE_2") (pintype "bidirectional"))
      (node (ref "U$4") (pin "5") (pinfunction "GND_5") (pintype "bidirectional"))
      (node (ref "U$5") (pin "5") (pinfunction "GND_5") (pintype "bidirectional"))
      (node (ref "U$6") (pin "15") (pinfunction "AVSS_15") (pintype "bidirectional"))
      (node (ref "U$6") (pin "4") (pinfunction "DVSS_4") (pintype "bidirectional"))
    )
    (net (code "35") (name "Net-(C1-Pad2)") (class "Default")
      (node (ref "C1") (pin "2") (pinfunction "2_2") (pintype "passive"))
      (node (ref "R34") (pin "2") (pinfunction "2_2") (pintype "passive"))
    )
    (net (code "36") (name "Net-(C5-Pad1)") (class "Default")
      (node (ref "C5") (pin "1") (pinfunction "1_1") (pintype "passive"))
      (node (ref "R32") (pin "1") (pinfunction "1_1") (pintype "passive"))
    )
    (net (code "37") (name "Net-(IC1A-+IN)") (class "Default")
      (node (ref "IC1") (pin "3") (pinfunction "+IN_3") (pintype "input"))
      (node (ref "R30") (pin "1") (pinfunction "1_1") (pintype "passive"))
      (node (ref "R5") (pin "2") (pinfunction "2_2") (pintype "passive"))
    )
    (net (code "38") (name "Net-(IC1A--IN)") (class "Default")
      (node (ref "IC1") (pin "2") (pinfunction "-IN_2") (pintype "input"))
      (node (ref "R31") (pin "1") (pinfunction "1_1") (pintype "passive"))
      (node (ref "R33") (pin "1") (pinfunction "1_1") (pintype "passive"))
    )
    (net (code "39") (name "Net-(IC1A-OUT)") (class "Default")
      (node (ref "IC1") (pin "1") (pinfunction "OUT_1") (pintype "output"))
      (node (ref "R33") (pin "2") (pinfunction "2_2") (pintype "passive"))
      (node (ref "R35") (pin "1") (pinfunction "1_1") (pintype "passive"))
    )
    (net (code "40") (name "Net-(IC1B--IN)") (class "Default")
      (node (ref "IC1") (pin "6") (pinfunction "-IN_6") (pintype "input"))
      (node (ref "R34") (pin "1") (pinfunction "1_1") (pintype "passive"))
      (node (ref "R35") (pin "2") (pinfunction "2_2") (pintype "passive"))
      (node (ref "R36") (pin "2") (pinfunction "2_2") (pintype "passive"))
    )
    (net (code "41") (name "Net-(IC5A-+IN)") (class "Default")
      (node (ref "IC5") (pin "3") (pinfunction "+IN_3") (pintype "input"))
      (node (ref "R14") (pin "1") (pinfunction "1_1") (pintype "passive"))
      (node (ref "R15") (pin "2") (pinfunction "2_2") (pintype "passive"))
    )
    (net (code "42") (name "Net-(IC5A--IN)") (class "Default")
      (node (ref "IC5") (pin "2") (pinfunction "-IN_2") (pintype "input"))
      (node (ref "R17") (pin "1") (pinfunction "1_1") (pintype "passive"))
      (node (ref "R18") (pin "2") (pinfunction "2_2") (pintype "passive"))
    )
    (net (code "43") (name "Net-(IC5A-OUT)") (class "Default")
      (node (ref "IC5") (pin "1") (pinfunction "OUT_1") (pintype "output"))
      (node (ref "R16") (pin "2") (pinfunction "2_2") (pintype "passive"))
      (node (ref "R18") (pin "1") (pinfunction "1_1") (pintype "passive"))
    )
    (net (code "44") (name "Net-(IC5B-+IN)") (class "Default")
      (node (ref "IC5") (pin "5") (pinfunction "+IN_5") (pintype "input"))
      (node (ref "R19") (pin "1") (pinfunction "1_1") (pintype "passive"))
      (node (ref "R20") (pin "2") (pinfunction "2_2") (pintype "passive"))
    )
    (net (code "45") (name "Net-(IC5B--IN)") (class "Default")
      (node (ref "IC5") (pin "6") (pinfunction "-IN_6") (pintype "input"))
      (node (ref "R22") (pin "1") (pinfunction "1_1") (pintype "passive"))
      (node (ref "R23") (pin "2") (pinfunction "2_2") (pintype "passive"))
    )
    (net (code "46") (name "Net-(IC5B-OUT)") (class "Default")
      (node (ref "IC5") (pin "7") (pinfunction "OUT_7") (pintype "output"))
      (node (ref "R21") (pin "2") (pinfunction "2_2") (pintype "passive"))
      (node (ref "R23") (pin "1") (pinfunction "1_1") (pintype "passive"))
    )
    (net (code "47") (name "Net-(IC7A-+IN)") (class "Default")
      (node (ref "IC7") (pin "3") (pinfunction "+IN_3") (pintype "input"))
      (node (ref "R39") (pin "2") (pinfunction "2_2") (pintype "passive"))
      (node (ref "R40") (pin "1") (pinfunction "1_1") (pintype "passive"))
    )
    (net (code "48") (name "Net-(IC7A--IN)") (class "Default")
      (node (ref "IC7") (pin "2") (pinfunction "-IN_2") (pintype "input"))
      (node (ref "R38") (pin "2") (pinfunction "2_2") (pintype "passive"))
      (node (ref "R41") (pin "1") (pinfunction "1_1") (pintype "passive"))
    )
    (net (code "49") (name "Net-(IC7A-OUT)") (class "Default")
      (node (ref "IC7") (pin "1") (pinfunction "OUT_1") (pintype "output"))
      (node (ref "R36") (pin "1") (pinfunction "1_1") (pintype "passive"))
      (node (ref "R41") (pin "2") (pinfunction "2_2") (pintype "passive"))
    )
    (net (code "50") (name "Net-(IC7B-+IN)") (class "Default")
      (node (ref "IC7") (pin "5") (pinfunction "+IN_5") (pintype "input"))
      (node (ref "R25") (pin "2") (pinfunction "2_2") (pintype "passive"))
      (node (ref "R26") (pin "1") (pinfunction "1_1") (pintype "passive"))
    )
    (net (code "51") (name "Net-(IC7B--IN)") (class "Default")
      (node (ref "IC7") (pin "6") (pinfunction "-IN_6") (pintype "input"))
      (node (ref "R27") (pin "1") (pinfunction "1_1") (pintype "passive"))
      (node (ref "R28") (pin "2") (pinfunction "2_2") (pintype "passive"))
    )
    (net (code "52") (name "Net-(IC7B-OUT)") (class "Default")
      (node (ref "IC7") (pin "7") (pinfunction "OUT_7") (pintype "output"))
      (node (ref "R28") (pin "1") (pinfunction "1_1") (pintype "passive"))
      (node (ref "R29") (pin "2") (pinfunction "2_2") (pintype "passive"))
    )
    (net (code "53") (name "Net-(IC9A-+IN)") (class "Default")
      (node (ref "IC9") (pin "3") (pinfunction "+IN_3") (pintype "input"))
      (node (ref "R29") (pin "1") (pinfunction "1_1") (pintype "passive"))
    )
    (net (code "54") (name "Net-(IC9A-OUT)") (class "Default")
      (node (ref "IC9") (pin "1") (pinfunction "OUT_1") (pintype "output"))
      (node (ref "U$7") (pin "1") (pinfunction "B_1") (pintype "passive"))
    )
    (net (code "55") (name "Net-(Q2-G)") (class "Default")
      (node (ref "Q2") (pin "1") (pinfunction "G_1") (pintype "passive"))
      (node (ref "R1") (pin "1") (pinfunction "1_1") (pintype "passive"))
    )
    (net (code "56") (name "Net-(Q3-G)") (class "Default")
      (node (ref "Q3") (pin "1") (pinfunction "G_1") (pintype "passive"))
      (node (ref "R2") (pin "1") (pinfunction "1_1") (pintype "passive"))
    )
    (net (code "57") (name "Net-(Q4-G)") (class "Default")
      (node (ref "Q4") (pin "1") (pinfunction "G_1") (pintype "passive"))
      (node (ref "R3") (pin "1") (pinfunction "1_1") (pintype "passive"))
    )
    (net (code "58") (name "Net-(R24-Pad2)") (class "Default")
      (node (ref "R24") (pin "2") (pinfunction "2_2") (pintype "passive"))
      (node (ref "R25") (pin "1") (pinfunction "1_1") (pintype "passive"))
    )
    (net (code "59") (name "Net-(U$2-OUT)") (class "Default")
      (node (ref "R7") (pin "2") (pinfunction "2_2") (pintype "passive"))
      (node (ref "U$2") (pin "6") (pinfunction "OUT_6") (pintype "bidirectional"))
    )
    (net (code "60") (name "Net-(U$3-OUT)") (class "Default")
      (node (ref "R9") (pin "2") (pinfunction "2_2") (pintype "passive"))
      (node (ref "U$3") (pin "6") (pinfunction "OUT_6") (pintype "bidirectional"))
    )
    (net (code "61") (name "Net-(U$4-FB)") (class "Default")
      (node (ref "R11") (pin "2") (pinfunction "2_2") (pintype "passive"))
      (node (ref "R12") (pin "2") (pinfunction "2_2") (pintype "passive"))
      (node (ref "R4") (pin "1") (pinfunction "1_1") (pintype "passive"))
      (node (ref "U$4") (pin "8") (pinfunction "FB_8") (pintype "bidirectional"))
    )
    (net (code "62") (name "Net-(U$4-RT)") (class "Default")
      (node (ref "R10") (pin "1") (pinfunction "1_1") (pintype "passive"))
      (node (ref "U$4") (pin "1") (pinfunction "RT_1") (pintype "bidirectional"))
    )
    (net (code "63") (name "Net-(U$4-SW)") (class "Default")
      (node (ref "10UH") (pin "2") (pinfunction "2_2") (pintype "passive"))
      (node (ref "U$10") (pin "A") (pinfunction "A_A") (pintype "passive"))
      (node (ref "U$4") (pin "4") (pinfunction "SW_4") (pintype "bidirectional"))
    )
    (net (code "64") (name "Net-(U$4-VC)") (class "Default")
      (node (ref "C11") (pin "2") (pinfunction "2_2") (pintype "passive"))
      (node (ref "C5") (pin "2") (pinfunction "2_2") (pintype "passive"))
      (node (ref "U$4") (pin "9") (pinfunction "VC_9") (pintype "bidirectional"))
    )
    (net (code "65") (name "Net-(U$5-PG)") (class "Default")
      (node (ref "R13") (pin "2") (pinfunction "2_2") (pintype "passive"))
      (node (ref "U$5") (pin "2") (pinfunction "PG_2") (pintype "bidirectional"))
    )
    (net (code "66") (name "Net-(U$5-SW)") (class "Default")
      (node (ref "0.47UH") (pin "1") (pinfunction "1_1") (pintype "passive"))
      (node (ref "U$5") (pin "6") (pinfunction "SW_6") (pintype "bidirectional"))
    )
    (net (code "67") (name "Net-(U$6-XIN{slash}P2.6)") (class "Default")
      (node (ref "C15") (pin "1") (pinfunction "1_1") (pintype "passive"))
      (node (ref "Q1") (pin "1") (pinfunction "1_1") (pintype "passive"))
      (node (ref "U$6") (pin "6") (pinfunction "XIN/P2.6_6") (pintype "bidirectional"))
    )
    (net (code "68") (name "Net-(U$6-XOUT{slash}P2.7)") (class "Default")
      (node (ref "C14") (pin "1") (pinfunction "1_1") (pintype "passive"))
      (node (ref "Q1") (pin "2") (pinfunction "2_2") (pintype "passive"))
      (node (ref "U$6") (pin "5") (pinfunction "XOUT/P2.7_5") (pintype "bidirectional"))
    )
    (net (code "69") (name "VCC") (class "Default")
      (node (ref "0.47UH") (pin "2") (pinfunction "2_2") (pintype "passive"))
      (node (ref "10UH") (pin "1") (pinfunction "1_1") (pintype "passive"))
      (node (ref "C10") (pin "2") (pinfunction "2_2") (pintype "passive"))
      (node (ref "C21") (pin "2") (pinfunction "2_2") (pintype "passive"))
      (node (ref "C27") (pin "2") (pinfunction "2_2") (pintype "passive"))
      (node (ref "C4") (pin "2") (pinfunction "2_2") (pintype "passive"))
      (node (ref "C_IC1") (pin "2") (pinfunction "2_2") (pintype "passive"))
      (node (ref "C_IC5") (pin "2") (pinfunction "2_2") (pintype "passive"))
      (node (ref "C_IC7") (pin "2") (pinfunction "2_2") (pintype "passive"))
      (node (ref "C_IC9") (pin "2") (pinfunction "2_2") (pintype "passive"))
      (node (ref "FERRITE_BEAD") (pin "2") (pinfunction "2_2") (pintype "passive"))
      (node (ref "IC1") (pin "8") (pinfunction "V+_8") (pintype "power_in"))
      (node (ref "IC5") (pin "8") (pinfunction "V+_8") (pintype "power_in"))
      (node (ref "IC7") (pin "8") (pinfunction "V+_8") (pintype "power_in"))
      (node (ref "IC9") (pin "8") (pinfunction "V+_8") (pintype "power_in"))
      (node (ref "R13") (pin "1") (pinfunction "1_1") (pintype "passive"))
      (node (ref "R14") (pin "2") (pinfunction "2_2") (pintype "passive"))
      (node (ref "R24") (pin "1") (pinfunction "1_1") (pintype "passive"))
      (node (ref "R5") (pin "1") (pinfunction "1_1") (pintype "passive"))
      (node (ref "R6") (pin "1") (pinfunction "1_1") (pintype "passive"))
      (node (ref "R79") (pin "1") (pinfunction "1_1") (pintype "passive"))
      (node (ref "R8") (pin "2") (pinfunction "2_2") (pintype "passive"))
      (node (ref "R80") (pin "1") (pinfunction "1_1") (pintype "passive"))
      (node (ref "R81") (pin "1") (pinfunction "1_1") (pintype "passive"))
      (node (ref "U$19") (pin "3") (pinfunction "VIN_3") (pintype "bidirectional"))
      (node (ref "U$2") (pin "3") (pinfunction "VCC_3") (pintype "bidirectional"))
      (node (ref "U$2") (pin "4") (pinfunction "IN+_4") (pintype "bidirectional"))
      (node (ref "U$3") (pin "3") (pinfunction "VCC_3") (pintype "bidirectional"))
      (node (ref "U$3") (pin "5") (pinfunction "IN-_5") (pintype "bidirectional"))
      (node (ref "U$4") (pin "3") (pinfunction "VIN_3") (pintype "bidirectional"))
      (node (ref "U$5") (pin "3") (pinfunction "FB_3") (pintype "bidirectional"))
      (node (ref "U$5") (pin "4") (pinfunction "VOS_4") (pintype "bidirectional"))
      (node (ref "U$6") (pin "16") (pinfunction "AVCC_16") (pintype "bidirectional"))
      (node (ref "U$7") (pin "2") (pinfunction "C_2") (pintype "passive"))
    )
    (net (code "70") (name "unconnected-(U$4-PG-Pad6)") (class "Default")
      (node (ref "U$4") (pin "6") (pinfunction "PG_6") (pintype "bidirectional"))
    )
    (net (code "71") (name "unconnected-(U$6-P1.0{slash}TACLK{slash}ADC10CLK-Pad31)") (class "Default")
      (node (ref "U$6") (pin "31") (pinfunction "P1.0/TACLK/ADC10CLK_31") (pintype "bidirectional"))
    )
    (net (code "72") (name "unconnected-(U$6-P1.5{slash}TA0{slash}TMS-Pad36)") (class "Default")
      (node (ref "U$6") (pin "36") (pinfunction "P1.5/TA0/TMS_36") (pintype "bidirectional"))
    )
    (net (code "73") (name "unconnected-(U$6-P1.6{slash}TA1{slash}TDI-Pad37)") (class "Default")
      (node (ref "U$6") (pin "37") (pinfunction "P1.6/TA1/TDI_37") (pintype "bidirectional"))
    )
    (net (code "74") (name "unconnected-(U$6-P1.7{slash}TA2{slash}TDO{slash}TDI-Pad38)") (class "Default")
      (node (ref "U$6") (pin "38") (pinfunction "P1.7/TA2/TDO/TDI_38") (pintype "bidirectional"))
    )
    (net (code "75") (name "unconnected-(U$6-P2.0{slash}ACLK{slash}A0-Pad8)") (class "Default")
      (node (ref "U$6") (pin "8") (pinfunction "P2.0/ACLK/A0_8") (pintype "bidirectional"))
    )
    (net (code "76") (name "unconnected-(U$6-P2.3{slash}TA1{slash}A3{slash}VREF−{slash}VEREF--Pad29)") (class "Default")
      (node (ref "U$6") (pin "29") (pinfunction "P2.3/TA1/A3/VREF−/VEREF-_29") (pintype "bidirectional"))
    )
    (net (code "77") (name "unconnected-(U$6-P2.4{slash}TA2{slash}A4{slash}VREF+{slash}VEREF+-Pad30)") (class "Default")
      (node (ref "U$6") (pin "30") (pinfunction "P2.4/TA2/A4/VREF+/VEREF+_30") (pintype "bidirectional"))
    )
    (net (code "78") (name "unconnected-(U$6-P2.5{slash}ROSC-Pad3)") (class "Default")
      (node (ref "U$6") (pin "3") (pinfunction "P2.5/ROSC_3") (pintype "bidirectional"))
    )
    (net (code "79") (name "unconnected-(U$6-P3.0{slash}UCB0STE{slash}UCA0CLK{slash}A5-Pad11)") (class "Default")
      (node (ref "U$6") (pin "11") (pinfunction "P3.0/UCB0STE/UCA0CLK/A5_11") (pintype "bidirectional"))
    )
    (net (code "80") (name "unconnected-(U$6-P3.3{slash}UCB0CLK{slash}UCA0STE-Pad14)") (class "Default")
      (node (ref "U$6") (pin "14") (pinfunction "P3.3/UCB0CLK/UCA0STE_14") (pintype "bidirectional"))
    )
    (net (code "81") (name "unconnected-(U$6-P3.4{slash}UCA0TXD{slash}UCA0SIMO-Pad25)") (class "Default")
      (node (ref "U$6") (pin "25") (pinfunction "P3.4/UCA0TXD/UCA0SIMO_25") (pintype "bidirectional"))
    )
    (net (code "82") (name "unconnected-(U$6-P3.5{slash}UCA0RXD{slash}UCA0SOMI-Pad26)") (class "Default")
      (node (ref "U$6") (pin "26") (pinfunction "P3.5/UCA0RXD/UCA0SOMI_26") (pintype "bidirectional"))
    )
    (net (code "83") (name "unconnected-(U$6-P4.7{slash}TBCLK-Pad24)") (class "Default")
      (node (ref "U$6") (pin "24") (pinfunction "P4.7/TBCLK_24") (pintype "bidirectional"))
    )
    (net (code "84") (name "unconnected-(U$16-OC-Pad5)") (class "Default")
      (node (ref "U$16") (pin "5") (pinfunction "OC_5") (pintype "bidirectional"))
    )
    (net (code "85") (name "unconnected-(U$17-OC-Pad5)") (class "Default")
      (node (ref "U$17") (pin "5") (pinfunction "OC_5") (pintype "bidirectional"))
    )
    (net (code "86") (name "unconnected-(U$18-OC-Pad5)") (class "Default")
      (node (ref "U$18") (pin "5") (pinfunction "OC_5") (pintype "bidirectional"))
    )
    (net (code "87") (name "unconnected-(U$19-NC1-Pad1)") (class "Default")
      (node (ref "U$19") (pin "1") (pinfunction "NC1_1") (pintype "bidirectional"))
    )
    (net (code "88") (name "unconnected-(U$19-NC2-Pad5)") (class "Default")
      (node (ref "U$19") (pin "5") (pinfunction "NC2_5") (pintype "bidirectional"))
    )
    (net (code "89") (name "unconnected-(U$19-NC3-Pad6)") (class "Default")
      (node (ref "U$19") (pin "6") (pinfunction "NC3_6") (pintype "bidirectional"))
    )
  )
)
